# PlugV3.net
KiCad netlist of a schematic drawn in EAGLE
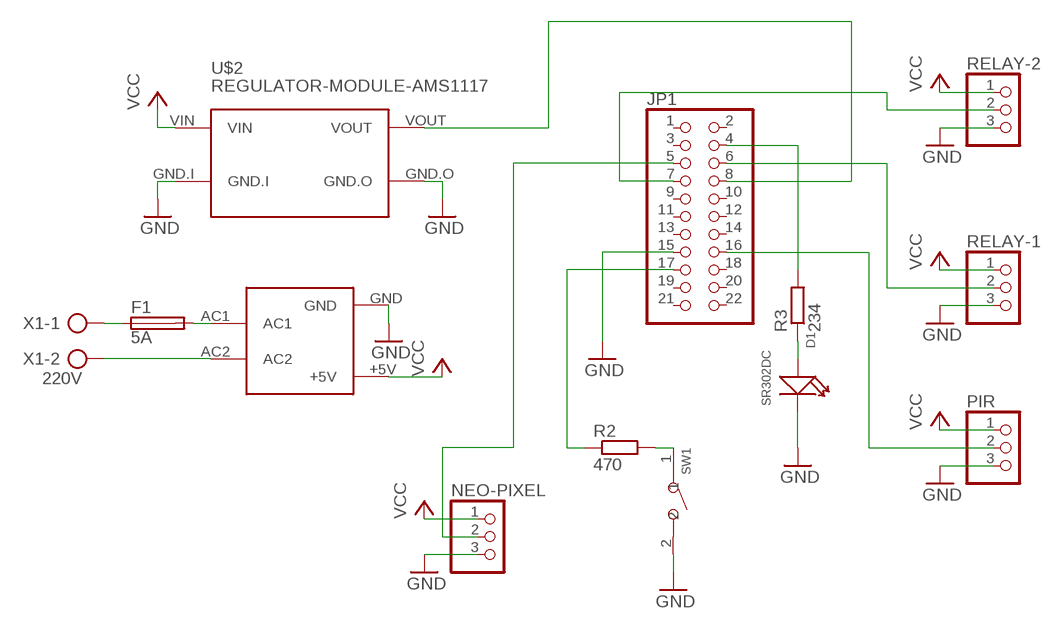
[diagram p0: schematic, sheet 1]

(export (version "E")
  (design (tool "Eeschema 10.0.6"))
  (components
    (comp (ref "D1")
      (value "SR302DC")
      (footprint "eagle-import:LED2-2.54-D3.0MM")
      (libsource (lib "eagle-import") (part "DIP-LED-RED-RED(2P-D3MM)"))
    )
    (comp (ref "F1")
      (value "5A")
      (footprint "eagle-import:SH22,5A")
      (fields (field (name "MPN") "0031.7701.11"))
      (libsource (lib "eagle-import") (part "SH22,5A"))
    )
    (comp (ref "JP1")
      (value "PINHD-2X11")
      (footprint "eagle-import:2X11")
      (libsource (lib "eagle-import") (part "PINHD-2X11"))
    )
    (comp (ref "NEO-PIXEL")
      (value "PINHD-1X3")
      (footprint "eagle-import:1X03")
      (libsource (lib "eagle-import") (part "PINHD-1X3"))
    )
    (comp (ref "PIR")
      (value "PINHD-1X3")
      (footprint "eagle-import:1X03")
      (libsource (lib "eagle-import") (part "PINHD-1X3"))
    )
    (comp (ref "R2")
      (value "470")
      (footprint "eagle-import:0207_7")
      (libsource (lib "eagle-import") (part "R-EU_0207/7"))
    )
    (comp (ref "R3")
      (value "234")
      (footprint "eagle-import:0207_7")
      (libsource (lib "eagle-import") (part "R-EU_0207/7"))
    )
    (comp (ref "RELAY-1")
      (value "PINHD-1X3")
      (footprint "eagle-import:1X03")
      (libsource (lib "eagle-import") (part "PINHD-1X3"))
    )
    (comp (ref "RELAY-2")
      (value "PINHD-1X3")
      (footprint "eagle-import:1X03")
      (libsource (lib "eagle-import") (part "PINHD-1X3"))
    )
    (comp (ref "SW1")
      (value "DIP-BUTTON(2P-6.0X3.0X4.3MM)-TS-1101F")
      (footprint "eagle-import:SW2-5.0-6.0X3.0X4.3MM")
      (libsource (lib "eagle-import") (part "DIP-BUTTON(2P-6.0X3.0X4.3MM)-TS-1101F"))
    )
    (comp (ref "U$1")
      (value "HLK-PM01")
      (footprint "eagle-import:HLK-PM01")
      (libsource (lib "eagle-import") (part "HLK-PM01"))
    )
    (comp (ref "U$2")
      (value "REGULATOR-MODULE-AMS1117")
      (footprint "eagle-import:REGULATOR-MODULE-AMS1117")
      (libsource (lib "eagle-import") (part "REGULATOR-MODULE-AMS1117"))
    )
    (comp (ref "X1")
      (value "220V")
      (footprint "eagle-import:AK300_2")
      (libsource (lib "eagle-import") (part "AK300/2"))
    )
  )
  (nets
    (net (code "1") (name "GND") (class "Default")
      (node (ref "D1") (pin "K") (pinfunction "-_K") (pintype "passive"))
      (node (ref "JP1") (pin "15") (pinfunction "15_15") (pintype "passive"))
      (node (ref "NEO-PIXEL") (pin "3") (pinfunction "3_3") (pintype "passive"))
      (node (ref "PIR") (pin "3") (pinfunction "3_3") (pintype "passive"))
      (node (ref "RELAY-1") (pin "3") (pinfunction "3_3") (pintype "passive"))
      (node (ref "RELAY-2") (pin "3") (pinfunction "3_3") (pintype "passive"))
      (node (ref "SW1") (pin "2") (pinfunction "2_2") (pintype "bidirectional"))
      (node (ref "U$1") (pin "GND") (pinfunction "GND_GND") (pintype "bidirectional"))
      (node (ref "U$2") (pin "GND.I") (pinfunction "GND.I_GND.I") (pintype "bidirectional"))
      (node (ref "U$2") (pin "GND.O") (pinfunction "GND.O_GND.O") (pintype "bidirectional"))
    )
    (net (code "2") (name "Net-(D1-+)") (class "Default")
      (node (ref "D1") (pin "A") (pinfunction "+_A") (pintype "passive"))
      (node (ref "R3") (pin "1") (pinfunction "1_1") (pintype "passive"))
    )
    (net (code "3") (name "Net-(F1-Pad2)") (class "Default")
      (node (ref "F1") (pin "2") (pinfunction "2_2") (pintype "passive"))
      (node (ref "U$1") (pin "AC1") (pinfunction "AC1_AC1") (pintype "bidirectional"))
    )
    (net (code "4") (name "Net-(JP1-Pad4)") (class "Default")
      (node (ref "JP1") (pin "4") (pinfunction "4_4") (pintype "passive"))
      (node (ref "R3") (pin "2") (pinfunction "2_2") (pintype "passive"))
    )
    (net (code "5") (name "Net-(JP1-Pad5)") (class "Default")
      (node (ref "JP1") (pin "5") (pinfunction "5_5") (pintype "passive"))
      (node (ref "NEO-PIXEL") (pin "2") (pinfunction "2_2") (pintype "passive"))
    )
    (net (code "6") (name "Net-(JP1-Pad6)") (class "Default")
      (node (ref "JP1") (pin "6") (pinfunction "6_6") (pintype "passive"))
      (node (ref "RELAY-1") (pin "2") (pinfunction "2_2") (pintype "passive"))
    )
    (net (code "7") (name "Net-(JP1-Pad7)") (class "Default")
      (node (ref "JP1") (pin "7") (pinfunction "7_7") (pintype "passive"))
      (node (ref "RELAY-2") (pin "2") (pinfunction "2_2") (pintype "passive"))
    )
    (net (code "8") (name "Net-(JP1-Pad8)") (class "Default")
      (node (ref "JP1") (pin "8") (pinfunction "8_8") (pintype "passive"))
      (node (ref "U$2") (pin "VOUT") (pinfunction "VOUT_VOUT") (pintype "bidirectional"))
    )
    (net (code "9") (name "Net-(JP1-Pad16)") (class "Default")
      (node (ref "JP1") (pin "16") (pinfunction "16_16") (pintype "passive"))
      (node (ref "PIR") (pin "2") (pinfunction "2_2") (pintype "passive"))
    )
    (net (code "10") (name "Net-(JP1-Pad17)") (class "Default")
      (node (ref "JP1") (pin "17") (pinfunction "17_17") (pintype "passive"))
      (node (ref "R2") (pin "1") (pinfunction "1_1") (pintype "passive"))
    )
    (net (code "11") (name "Net-(R2-Pad2)") (class "Default")
      (node (ref "R2") (pin "2") (pinfunction "2_2") (pintype "passive"))
      (node (ref "SW1") (pin "1") (pinfunction "1_1") (pintype "bidirectional"))
    )
    (net (code "12") (name "Net-(X1A-KL)") (class "Default")
      (node (ref "F1") (pin "1") (pinfunction "1_1") (pintype "passive"))
      (node (ref "X1") (pin "1") (pinfunction "KL_1") (pintype "passive"))
    )
    (net (code "13") (name "Net-(X1B-KL)") (class "Default")
      (node (ref "U$1") (pin "AC2") (pinfunction "AC2_AC2") (pintype "bidirectional"))
      (node (ref "X1") (pin "2") (pinfunction "KL_2") (pintype "passive"))
    )
    (net (code "14") (name "VCC") (class "Default")
      (node (ref "NEO-PIXEL") (pin "1") (pinfunction "1_1") (pintype "passive"))
      (node (ref "PIR") (pin "1") (pinfunction "1_1") (pintype "passive"))
      (node (ref "RELAY-1") (pin "1") (pinfunction "1_1") (pintype "passive"))
      (node (ref "RELAY-2") (pin "1") (pinfunction "1_1") (pintype "passive"))
      (node (ref "U$1") (pin "+5V") (pinfunction "+5V_+5V") (pintype "bidirectional"))
      (node (ref "U$2") (pin "VIN") (pinfunction "VIN_VIN") (pintype "bidirectional"))
    )
    (net (code "15") (name "unconnected-(JP1-Pad1)") (class "Default")
      (node (ref "JP1") (pin "1") (pinfunction "1_1") (pintype "passive"))
    )
    (net (code "16") (name "unconnected-(JP1-Pad2)") (class "Default")
      (node (ref "JP1") (pin "2") (pinfunction "2_2") (pintype "passive"))
    )
    (net (code "17") (name "unconnected-(JP1-Pad3)") (class "Default")
      (node (ref "JP1") (pin "3") (pinfunction "3_3") (pintype "passive"))
    )
    (net (code "18") (name "unconnected-(JP1-Pad9)") (class "Default")
      (node (ref "JP1") (pin "9") (pinfunction "9_9") (pintype "passive"))
    )
    (net (code "19") (name "unconnected-(JP1-Pad10)") (class "Default")
      (node (ref "JP1") (pin "10") (pinfunction "10_10") (pintype "passive"))
    )
    (net (code "20") (name "unconnected-(JP1-Pad11)") (class "Default")
      (node (ref "JP1") (pin "11") (pinfunction "11_11") (pintype "passive"))
    )
    (net (code "21") (name "unconnected-(JP1-Pad12)") (class "Default")
      (node (ref "JP1") (pin "12") (pinfunction "12_12") (pintype "passive"))
    )
    (net (code "22") (name "unconnected-(JP1-Pad13)") (class "Default")
      (node (ref "JP1") (pin "13") (pinfunction "13_13") (pintype "passive"))
    )
    (net (code "23") (name "unconnected-(JP1-Pad14)") (class "Default")
      (node (ref "JP1") (pin "14") (pinfunction "14_14") (pintype "passive"))
    )
    (net (code "24") (name "unconnected-(JP1-Pad18)") (class "Default")
      (node (ref "JP1") (pin "18") (pinfunction "18_18") (pintype "passive"))
    )
    (net (code "25") (name "unconnected-(JP1-Pad19)") (class "Default")
      (node (ref "JP1") (pin "19") (pinfunction "19_19") (pintype "passive"))
    )
    (net (code "26") (name "unconnected-(JP1-Pad20)") (class "Default")
      (node (ref "JP1") (pin "20") (pinfunction "20_20") (pintype "passive"))
    )
    (net (code "27") (name "unconnected-(JP1-Pad21)") (class "Default")
      (node (ref "JP1") (pin "21") (pinfunction "21_21") (pintype "passive"))
    )
    (net (code "28") (name "unconnected-(JP1-Pad22)") (class "Default")
      (node (ref "JP1") (pin "22") (pinfunction "22_22") (pintype "passive"))
    )
  )
)
